# Proto-Pi.net
KiCad netlist of a schematic drawn in EAGLE
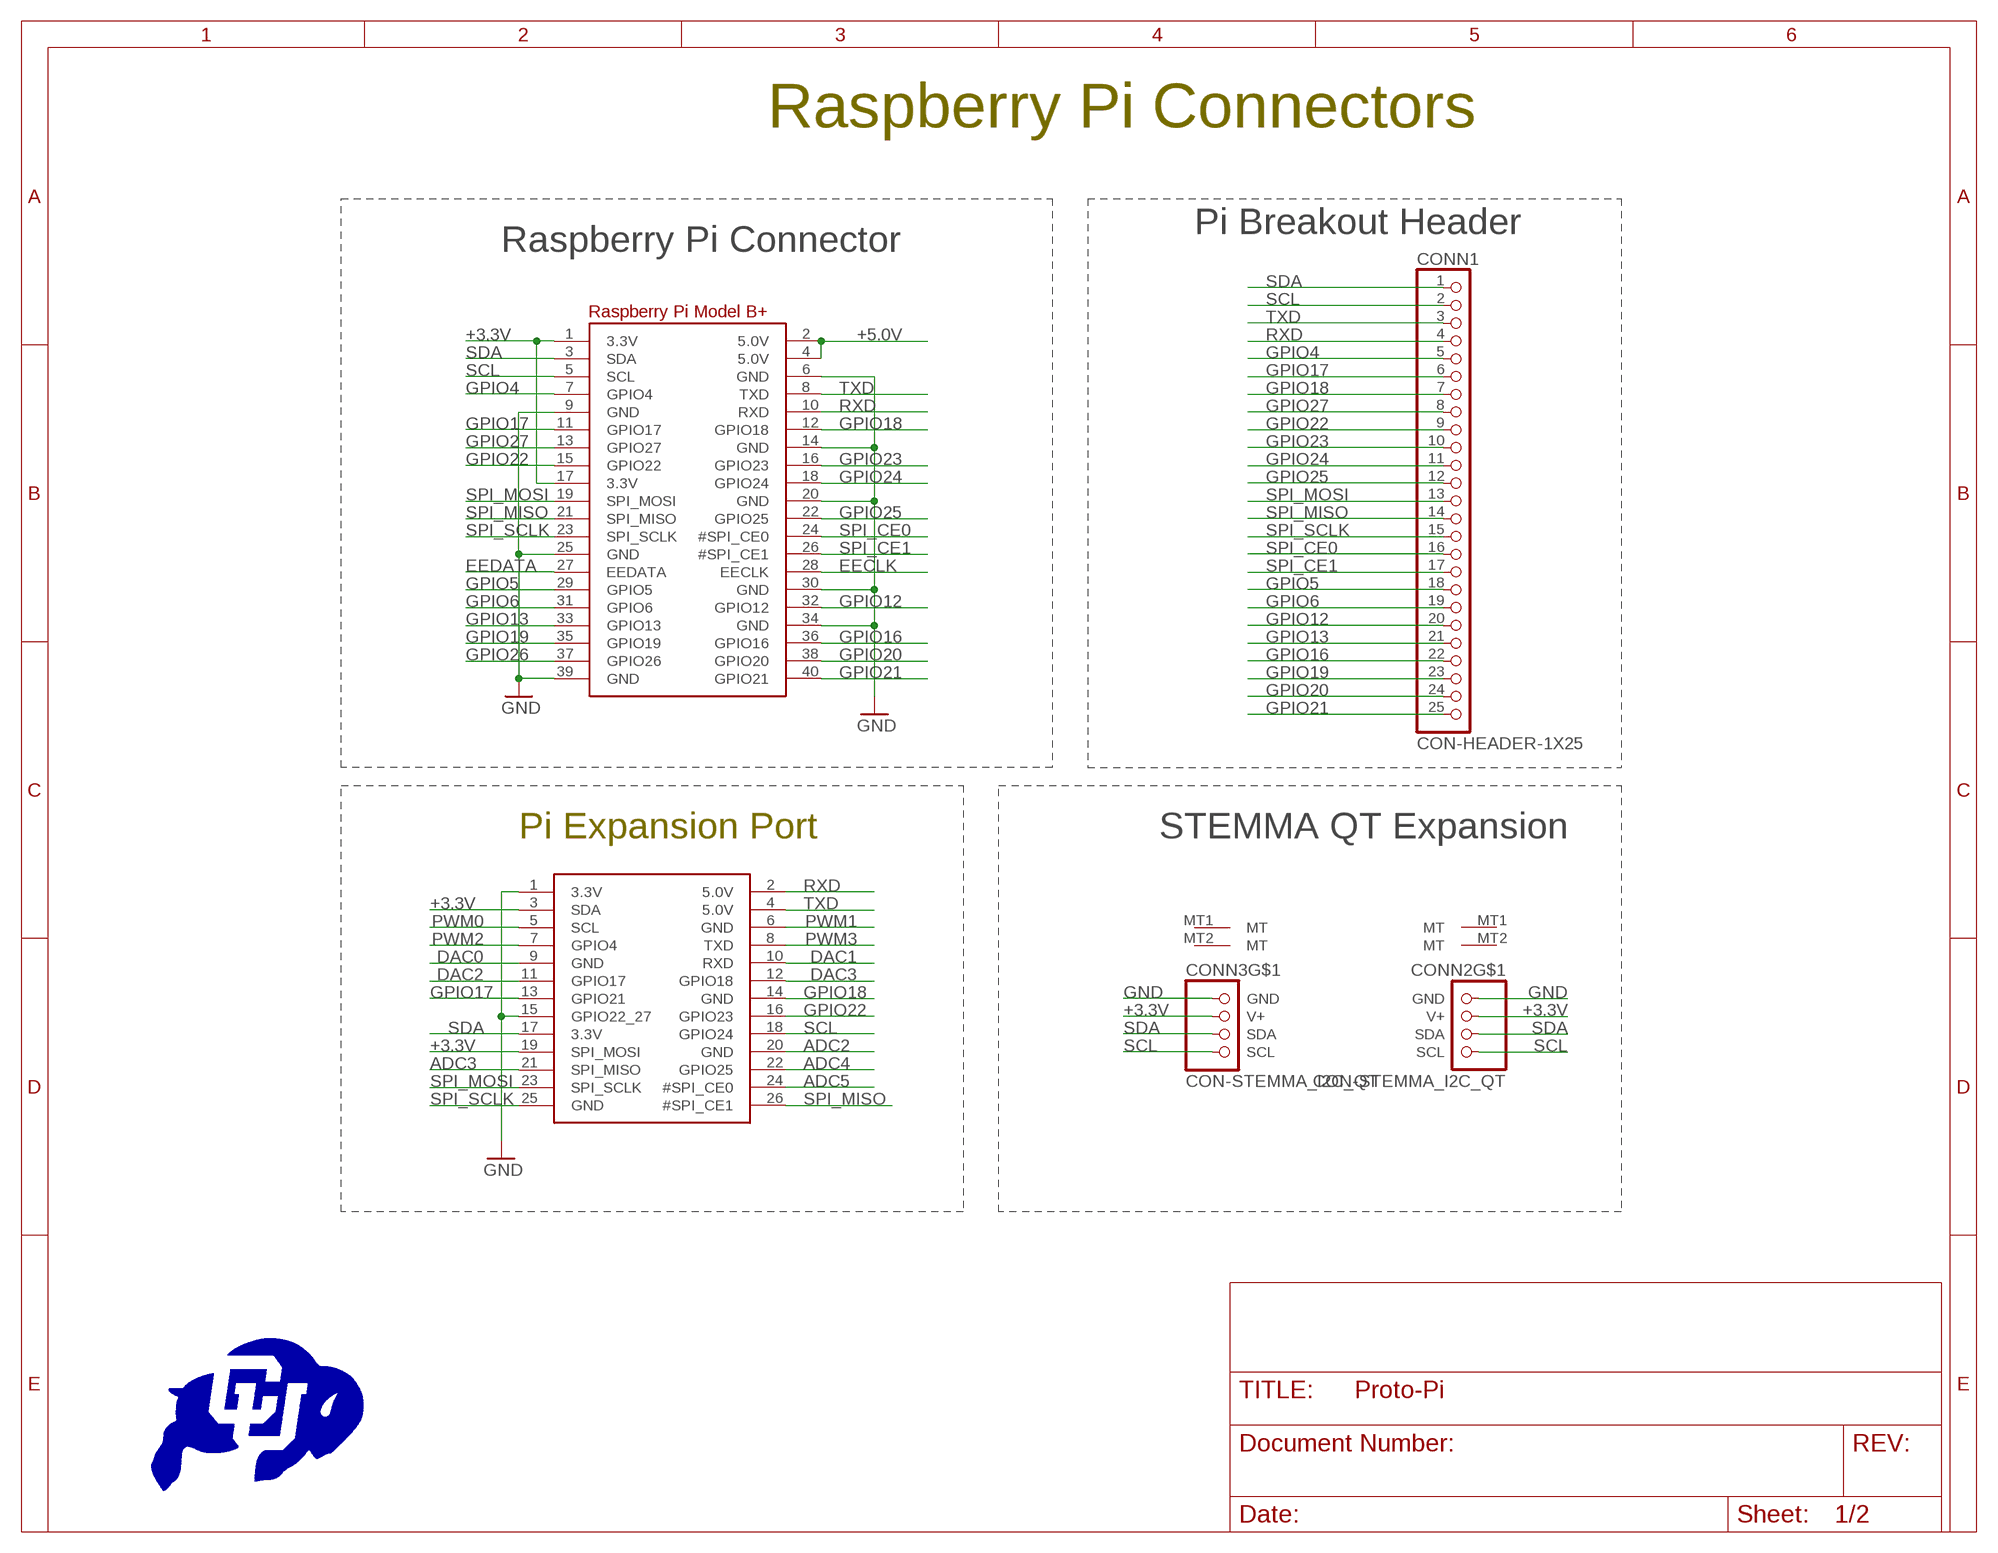
[diagram p0: schematic, sheet 1]
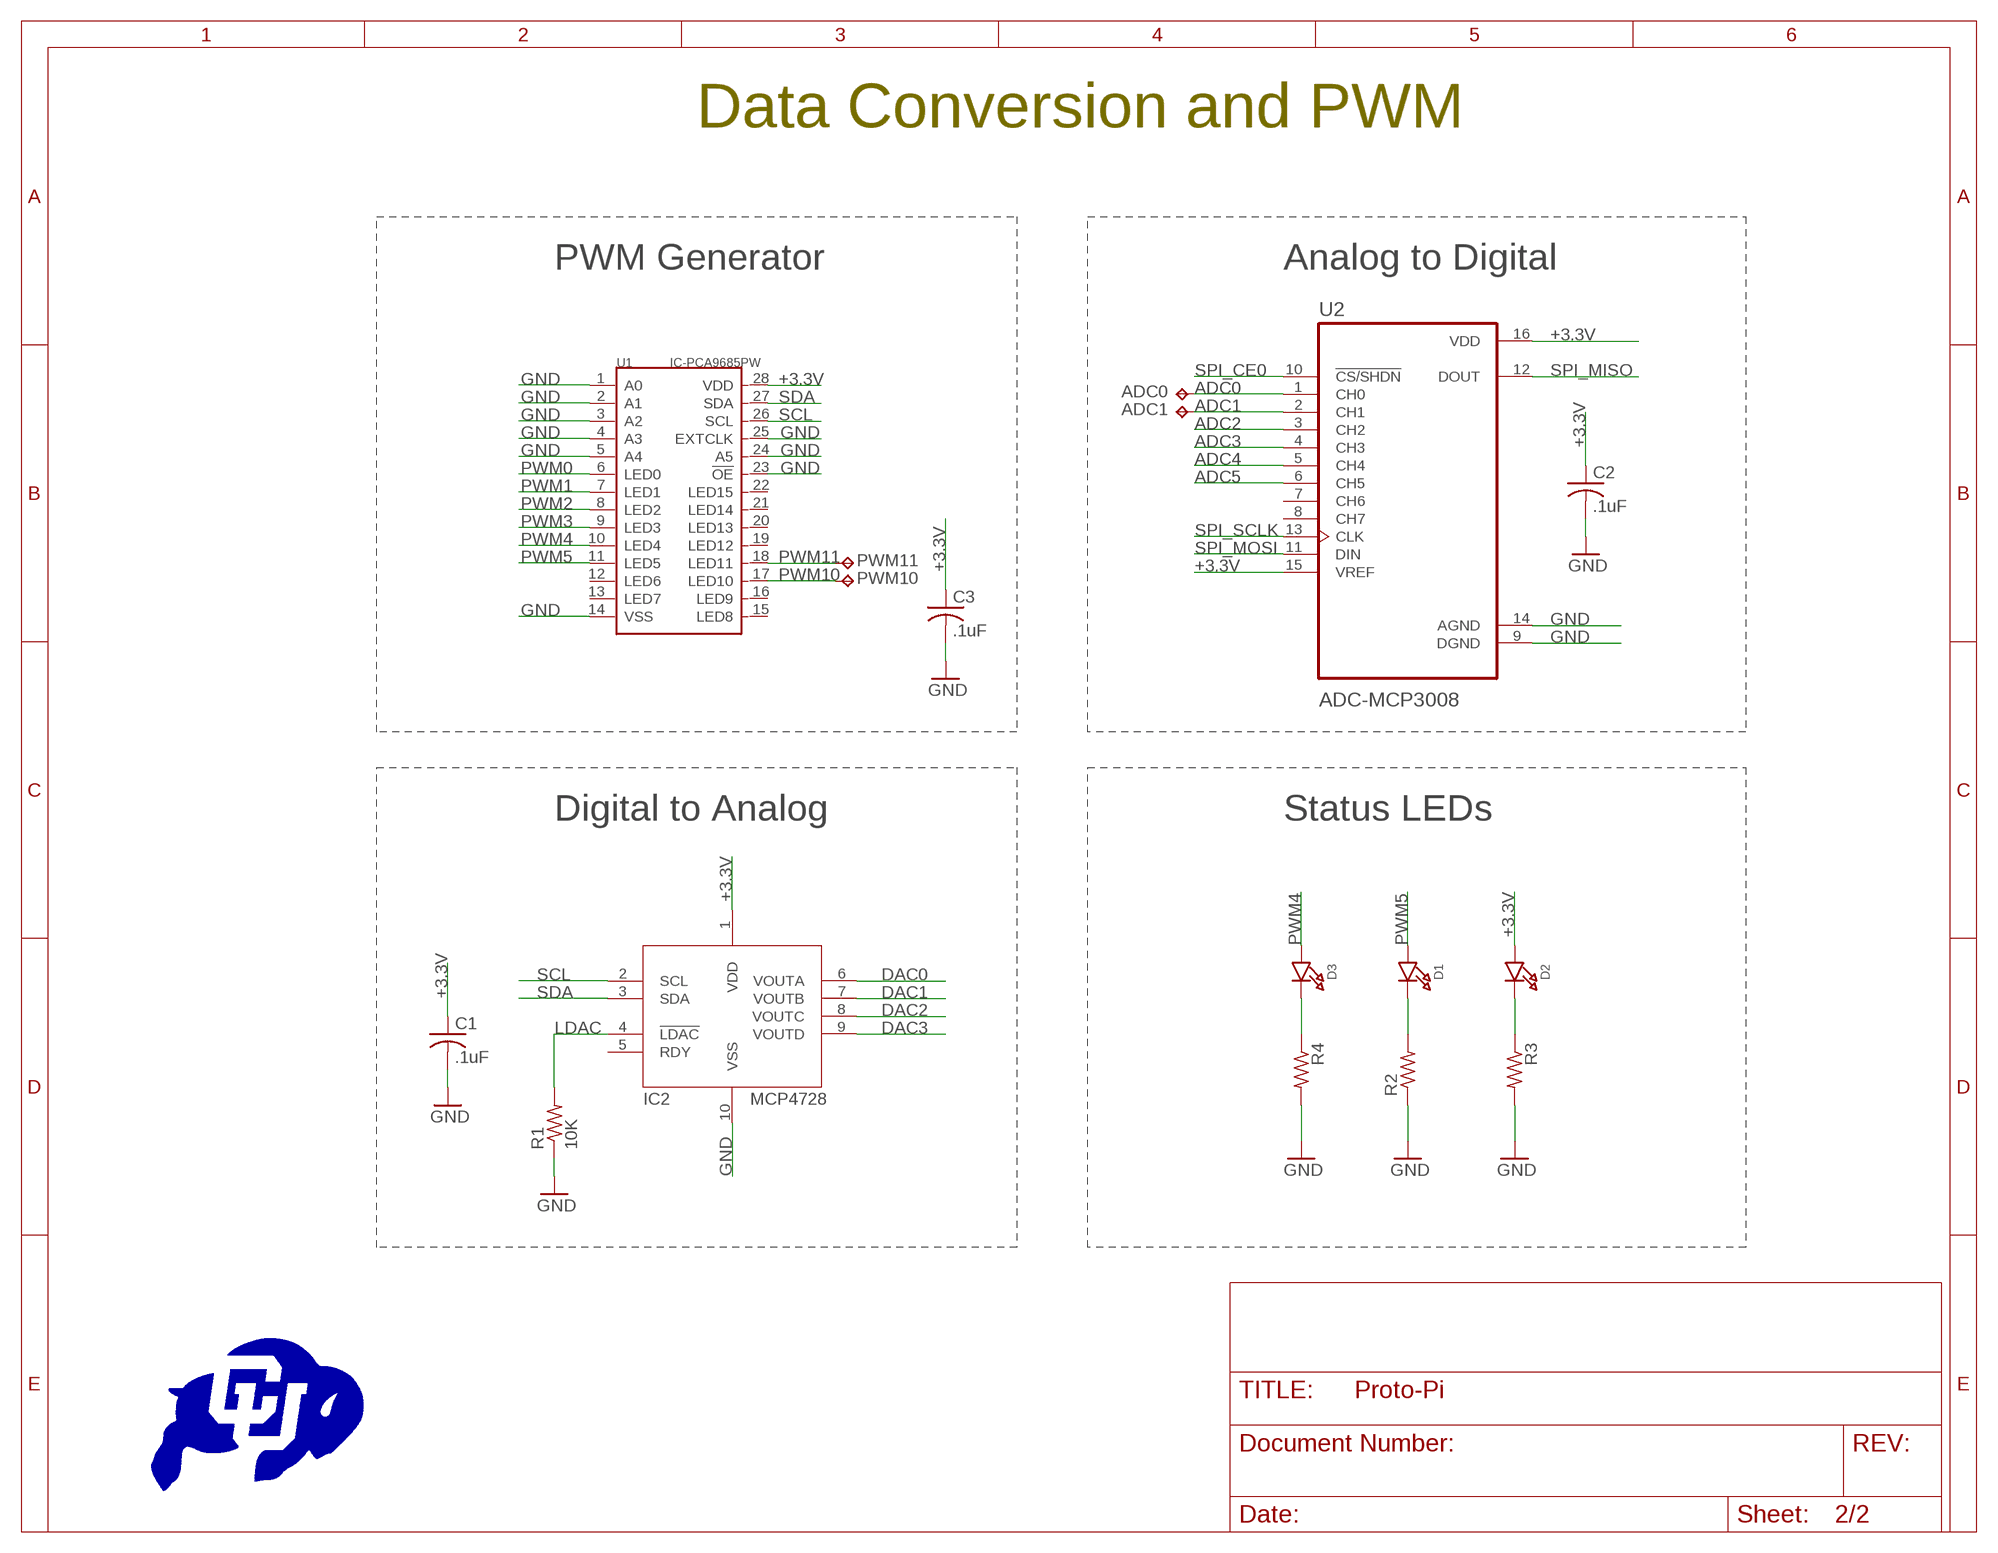
[diagram p1: schematic, sheet 2]

(export (version "E")
  (design (tool "Eeschema 10.0.6"))
  (components
    (comp (ref "CONN1")
      (value "CON-HEADER-1X25")
      (footprint "eagle-import:1X25_ROUND_70MIL")
      (libsource (lib "eagle-import") (part "CON-HEADER-1X25"))
    )
    (comp (ref "CONN2")
      (value "CON-STEMMA_I2C_QT")
      (footprint "eagle-import:JST_SH4")
      (libsource (lib "eagle-import") (part "CON-STEMMA_I2C_QT"))
    )
    (comp (ref "CONN3")
      (value "CON-STEMMA_I2C_QT")
      (footprint "eagle-import:JST_SH4")
      (libsource (lib "eagle-import") (part "CON-STEMMA_I2C_QT"))
    )
    (comp (ref "JP1")
      (value "CON-RASBERRYPI_IDC")
      (footprint "eagle-import:RASBERRYPI_IDC")
      (libsource (lib "eagle-import") (part "CON-RASBERRYPI_IDC"))
    )
    (comp (ref "P1")
      (value "ART-CU-LOGO")
      (footprint "eagle-import:CU_LOGO")
      (libsource (lib "eagle-import") (part "ART-CU-LOGO"))
    )
    (comp (ref "RPI1")
      (value "BRD-RASPBERRYPI_BPLUS_BONNETNODIM")
      (footprint "eagle-import:PI_BONNET_NODIM")
      (libsource (lib "eagle-import") (part "BRD-RASPBERRYPI_BPLUS_BONNETNODIM"))
    )
    (comp (ref "ADC0")
      (value "TPTP20R")
      (footprint "eagle-import:TP20R")
      (libsource (lib "eagle-import") (part "TPTP20R"))
    )
    (comp (ref "ADC1")
      (value "TPTP20R")
      (footprint "eagle-import:TP20R")
      (libsource (lib "eagle-import") (part "TPTP20R"))
    )
    (comp (ref "C1")
      (value ".1uF")
      (footprint "eagle-import:C0603")
      (fields (field (name "MANUFACTURER") "?"))
      (libsource (lib "eagle-import") (part "C-USC0603"))
    )
    (comp (ref "C2")
      (value ".1uF")
      (footprint "eagle-import:C0603")
      (fields (field (name "MANUFACTURER") "?"))
      (libsource (lib "eagle-import") (part "C-USC0603"))
    )
    (comp (ref "C3")
      (value ".1uF")
      (footprint "eagle-import:C0603")
      (fields (field (name "MANUFACTURER") "?"))
      (libsource (lib "eagle-import") (part "C-USC0603"))
    )
    (comp (ref "D1")
      (value "LED-SMA0603_NOOUTLINE")
      (footprint "eagle-import:CHIPLED_0603_NOOUTLINE")
      (libsource (lib "eagle-import") (part "LED-SMA0603_NOOUTLINE"))
    )
    (comp (ref "D2")
      (value "LED-SMA0603_NOOUTLINE")
      (footprint "eagle-import:CHIPLED_0603_NOOUTLINE")
      (libsource (lib "eagle-import") (part "LED-SMA0603_NOOUTLINE"))
    )
    (comp (ref "D3")
      (value "LED-SMA0603_NOOUTLINE")
      (footprint "eagle-import:CHIPLED_0603_NOOUTLINE")
      (libsource (lib "eagle-import") (part "LED-SMA0603_NOOUTLINE"))
    )
    (comp (ref "IC2")
      (value "DAC-MCP4728")
      (footprint "eagle-import:MSOP10")
      (fields (field (name "MANUFACTURER") "?"))
      (libsource (lib "eagle-import") (part "DAC-MCP4728"))
    )
    (comp (ref "P2")
      (value "ART-CU-LOGO")
      (footprint "eagle-import:CU_LOGO")
      (libsource (lib "eagle-import") (part "ART-CU-LOGO"))
    )
    (comp (ref "PWM10")
      (value "TPTP20R")
      (footprint "eagle-import:TP20R")
      (libsource (lib "eagle-import") (part "TPTP20R"))
    )
    (comp (ref "PWM11")
      (value "TPTP20R")
      (footprint "eagle-import:TP20R")
      (libsource (lib "eagle-import") (part "TPTP20R"))
    )
    (comp (ref "R1")
      (value "10K")
      (footprint "eagle-import:R0603")
      (fields (field (name "MANUFACTURER") "?"))
      (libsource (lib "eagle-import") (part "R-US_R0603"))
    )
    (comp (ref "R2")
      (value "R-US_R0402")
      (footprint "eagle-import:R0402")
      (fields (field (name "MANUFACTURER") "?"))
      (libsource (lib "eagle-import") (part "R-US_R0402"))
    )
    (comp (ref "R3")
      (value "R-US_R0402")
      (footprint "eagle-import:R0402")
      (fields (field (name "MANUFACTURER") "?"))
      (libsource (lib "eagle-import") (part "R-US_R0402"))
    )
    (comp (ref "R4")
      (value "R-US_R0402")
      (footprint "eagle-import:R0402")
      (fields (field (name "MANUFACTURER") "?"))
      (libsource (lib "eagle-import") (part "R-US_R0402"))
    )
    (comp (ref "U1")
      (value "IC-PCA9685PW")
      (footprint "eagle-import:TSSOP28-0.65-9.7X4.4MM")
      (fields (field (name "MANUFACTURER") "?"))
      (libsource (lib "eagle-import") (part "IC-PCA9685PW"))
    )
    (comp (ref "U2")
      (value "ADC-MCP3008")
      (footprint "eagle-import:SOIC127P600X175-16N")
      (fields (field (name "MANUFACTURER") "?"))
      (libsource (lib "eagle-import") (part "ADC-MCP3008"))
    )
  )
  (nets
    (net (code "1") (name "+3.3V") (class "Default")
      (node (ref "C1") (pin "1") (pinfunction "1_1") (pintype "passive"))
      (node (ref "C2") (pin "1") (pinfunction "1_1") (pintype "passive"))
      (node (ref "C3") (pin "1") (pinfunction "1_1") (pintype "passive"))
      (node (ref "CONN2") (pin "2") (pinfunction "V+_2") (pintype "passive"))
      (node (ref "CONN3") (pin "2") (pinfunction "V+_2") (pintype "passive"))
      (node (ref "D2") (pin "A") (pinfunction "A_A") (pintype "passive"))
      (node (ref "IC2") (pin "1") (pinfunction "VDD_1") (pintype "power_in"))
      (node (ref "JP1") (pin "19") (pinfunction "SPI_MOSI_19") (pintype "bidirectional"))
      (node (ref "JP1") (pin "3") (pinfunction "SDA_3") (pintype "bidirectional"))
      (node (ref "RPI1") (pin "1") (pinfunction "3.3V_1") (pintype "power_in"))
      (node (ref "RPI1") (pin "17") (pinfunction "3.3V_17") (pintype "power_in"))
      (node (ref "U1") (pin "28") (pinfunction "VDD_28") (pintype "bidirectional"))
      (node (ref "U2") (pin "15") (pinfunction "VREF_15") (pintype "input"))
      (node (ref "U2") (pin "16") (pinfunction "VDD_16") (pintype "power_in"))
    )
    (net (code "2") (name "+5.0V") (class "Default")
      (node (ref "RPI1") (pin "2") (pinfunction "5.0V_2") (pintype "power_in"))
      (node (ref "RPI1") (pin "4") (pinfunction "5.0V_4") (pintype "power_in"))
    )
    (net (code "3") (name "ADC0") (class "Default")
      (node (ref "ADC0") (pin "TP") (pinfunction "TP_TP") (pintype "input"))
      (node (ref "U2") (pin "1") (pinfunction "CH0_1") (pintype "input"))
    )
    (net (code "4") (name "ADC1") (class "Default")
      (node (ref "ADC1") (pin "TP") (pinfunction "TP_TP") (pintype "input"))
      (node (ref "U2") (pin "2") (pinfunction "CH1_2") (pintype "input"))
    )
    (net (code "5") (name "ADC2") (class "Default")
      (node (ref "JP1") (pin "20") (pinfunction "GND_20") (pintype "power_in"))
      (node (ref "U2") (pin "3") (pinfunction "CH2_3") (pintype "input"))
    )
    (net (code "6") (name "ADC3") (class "Default")
      (node (ref "JP1") (pin "21") (pinfunction "SPI_MISO_21") (pintype "input"))
      (node (ref "U2") (pin "4") (pinfunction "CH3_4") (pintype "input"))
    )
    (net (code "7") (name "ADC4") (class "Default")
      (node (ref "JP1") (pin "22") (pinfunction "GPIO25_22") (pintype "bidirectional"))
      (node (ref "U2") (pin "5") (pinfunction "CH4_5") (pintype "input"))
    )
    (net (code "8") (name "ADC5") (class "Default")
      (node (ref "JP1") (pin "24") (pinfunction "#SPI_CE0_24") (pintype "bidirectional"))
      (node (ref "U2") (pin "6") (pinfunction "CH5_6") (pintype "input"))
    )
    (net (code "9") (name "DAC0") (class "Default")
      (node (ref "IC2") (pin "6") (pinfunction "VOUTA_6") (pintype "output"))
      (node (ref "JP1") (pin "9") (pinfunction "GND_9") (pintype "power_in"))
    )
    (net (code "10") (name "DAC1") (class "Default")
      (node (ref "IC2") (pin "7") (pinfunction "VOUTB_7") (pintype "output"))
      (node (ref "JP1") (pin "10") (pinfunction "RXD_10") (pintype "input"))
    )
    (net (code "11") (name "DAC2") (class "Default")
      (node (ref "IC2") (pin "8") (pinfunction "VOUTC_8") (pintype "output"))
      (node (ref "JP1") (pin "11") (pinfunction "GPIO17_11") (pintype "bidirectional"))
    )
    (net (code "12") (name "DAC3") (class "Default")
      (node (ref "IC2") (pin "9") (pinfunction "VOUTD_9") (pintype "output"))
      (node (ref "JP1") (pin "12") (pinfunction "GPIO18_12") (pintype "bidirectional"))
    )
    (net (code "13") (name "EECLK") (class "Default")
      (node (ref "RPI1") (pin "28") (pinfunction "EECLK_28") (pintype "bidirectional"))
    )
    (net (code "14") (name "EEDATA") (class "Default")
      (node (ref "RPI1") (pin "27") (pinfunction "EEDATA_27") (pintype "bidirectional"))
    )
    (net (code "15") (name "GND") (class "Default")
      (node (ref "C1") (pin "2") (pinfunction "2_2") (pintype "passive"))
      (node (ref "C2") (pin "2") (pinfunction "2_2") (pintype "passive"))
      (node (ref "C3") (pin "2") (pinfunction "2_2") (pintype "passive"))
      (node (ref "CONN2") (pin "1") (pinfunction "GND_1") (pintype "passive"))
      (node (ref "CONN3") (pin "1") (pinfunction "GND_1") (pintype "passive"))
      (node (ref "IC2") (pin "10") (pinfunction "VSS_10") (pintype "power_in"))
      (node (ref "JP1") (pin "1") (pinfunction "3.3V_1") (pintype "power_in"))
      (node (ref "JP1") (pin "15") (pinfunction "GPIO22_27_15") (pintype "bidirectional"))
      (node (ref "R1") (pin "1") (pinfunction "1_1") (pintype "passive"))
      (node (ref "R2") (pin "1") (pinfunction "1_1") (pintype "passive"))
      (node (ref "R3") (pin "2") (pinfunction "2_2") (pintype "passive"))
      (node (ref "R4") (pin "2") (pinfunction "2_2") (pintype "passive"))
      (node (ref "RPI1") (pin "14") (pinfunction "GND_14") (pintype "power_in"))
      (node (ref "RPI1") (pin "20") (pinfunction "GND_20") (pintype "power_in"))
      (node (ref "RPI1") (pin "25") (pinfunction "GND_25") (pintype "power_in"))
      (node (ref "RPI1") (pin "30") (pinfunction "GND_30") (pintype "power_in"))
      (node (ref "RPI1") (pin "34") (pinfunction "GND_34") (pintype "power_in"))
      (node (ref "RPI1") (pin "39") (pinfunction "GND_39") (pintype "power_in"))
      (node (ref "RPI1") (pin "6") (pinfunction "GND_6") (pintype "power_in"))
      (node (ref "RPI1") (pin "9") (pinfunction "GND_9") (pintype "power_in"))
      (node (ref "U1") (pin "1") (pinfunction "A0_1") (pintype "bidirectional"))
      (node (ref "U1") (pin "14") (pinfunction "VSS_14") (pintype "bidirectional"))
      (node (ref "U1") (pin "2") (pinfunction "A1_2") (pintype "bidirectional"))
      (node (ref "U1") (pin "23") (pinfunction "~{OE}_23") (pintype "bidirectional"))
      (node (ref "U1") (pin "24") (pinfunction "A5_24") (pintype "bidirectional"))
      (node (ref "U1") (pin "25") (pinfunction "EXTCLK_25") (pintype "bidirectional"))
      (node (ref "U1") (pin "3") (pinfunction "A2_3") (pintype "bidirectional"))
      (node (ref "U1") (pin "4") (pinfunction "A3_4") (pintype "bidirectional"))
      (node (ref "U1") (pin "5") (pinfunction "A4_5") (pintype "bidirectional"))
      (node (ref "U2") (pin "14") (pinfunction "AGND_14") (pintype "power_in"))
      (node (ref "U2") (pin "9") (pinfunction "DGND_9") (pintype "power_in"))
    )
    (net (code "16") (name "GPIO4") (class "Default")
      (node (ref "CONN1") (pin "5") (pinfunction "5_5") (pintype "passive"))
      (node (ref "RPI1") (pin "7") (pinfunction "GPIO4_7") (pintype "bidirectional"))
    )
    (net (code "17") (name "GPIO5") (class "Default")
      (node (ref "CONN1") (pin "18") (pinfunction "18_18") (pintype "passive"))
      (node (ref "RPI1") (pin "29") (pinfunction "GPIO5_29") (pintype "bidirectional"))
    )
    (net (code "18") (name "GPIO6") (class "Default")
      (node (ref "CONN1") (pin "19") (pinfunction "19_19") (pintype "passive"))
      (node (ref "RPI1") (pin "31") (pinfunction "GPIO6_31") (pintype "bidirectional"))
    )
    (net (code "19") (name "GPIO12") (class "Default")
      (node (ref "CONN1") (pin "20") (pinfunction "20_20") (pintype "passive"))
      (node (ref "RPI1") (pin "32") (pinfunction "GPIO12_32") (pintype "bidirectional"))
    )
    (net (code "20") (name "GPIO13") (class "Default")
      (node (ref "CONN1") (pin "21") (pinfunction "21_21") (pintype "passive"))
      (node (ref "RPI1") (pin "33") (pinfunction "GPIO13_33") (pintype "bidirectional"))
    )
    (net (code "21") (name "GPIO16") (class "Default")
      (node (ref "CONN1") (pin "22") (pinfunction "22_22") (pintype "passive"))
      (node (ref "RPI1") (pin "36") (pinfunction "GPIO16_36") (pintype "bidirectional"))
    )
    (net (code "22") (name "GPIO17") (class "Default")
      (node (ref "CONN1") (pin "6") (pinfunction "6_6") (pintype "passive"))
      (node (ref "JP1") (pin "13") (pinfunction "GPIO21_13") (pintype "bidirectional"))
      (node (ref "RPI1") (pin "11") (pinfunction "GPIO17_11") (pintype "bidirectional"))
    )
    (net (code "23") (name "GPIO18") (class "Default")
      (node (ref "CONN1") (pin "7") (pinfunction "7_7") (pintype "passive"))
      (node (ref "JP1") (pin "14") (pinfunction "GND_14") (pintype "power_in"))
      (node (ref "RPI1") (pin "12") (pinfunction "GPIO18_12") (pintype "bidirectional"))
    )
    (net (code "24") (name "GPIO19") (class "Default")
      (node (ref "CONN1") (pin "23") (pinfunction "23_23") (pintype "passive"))
      (node (ref "RPI1") (pin "35") (pinfunction "GPIO19_35") (pintype "bidirectional"))
    )
    (net (code "25") (name "GPIO20") (class "Default")
      (node (ref "CONN1") (pin "24") (pinfunction "24_24") (pintype "passive"))
      (node (ref "RPI1") (pin "38") (pinfunction "GPIO20_38") (pintype "bidirectional"))
    )
    (net (code "26") (name "GPIO21") (class "Default")
      (node (ref "CONN1") (pin "25") (pinfunction "25_25") (pintype "passive"))
      (node (ref "RPI1") (pin "40") (pinfunction "GPIO21_40") (pintype "bidirectional"))
    )
    (net (code "27") (name "GPIO22") (class "Default")
      (node (ref "CONN1") (pin "9") (pinfunction "9_9") (pintype "passive"))
      (node (ref "JP1") (pin "16") (pinfunction "GPIO23_16") (pintype "bidirectional"))
      (node (ref "RPI1") (pin "15") (pinfunction "GPIO22_15") (pintype "bidirectional"))
    )
    (net (code "28") (name "GPIO23") (class "Default")
      (node (ref "CONN1") (pin "10") (pinfunction "10_10") (pintype "passive"))
      (node (ref "RPI1") (pin "16") (pinfunction "GPIO23_16") (pintype "bidirectional"))
    )
    (net (code "29") (name "GPIO24") (class "Default")
      (node (ref "CONN1") (pin "11") (pinfunction "11_11") (pintype "passive"))
      (node (ref "RPI1") (pin "18") (pinfunction "GPIO24_18") (pintype "bidirectional"))
    )
    (net (code "30") (name "GPIO25") (class "Default")
      (node (ref "CONN1") (pin "12") (pinfunction "12_12") (pintype "passive"))
      (node (ref "RPI1") (pin "22") (pinfunction "GPIO25_22") (pintype "bidirectional"))
    )
    (net (code "31") (name "GPIO26") (class "Default")
      (node (ref "RPI1") (pin "37") (pinfunction "GPIO26_37") (pintype "bidirectional"))
    )
    (net (code "32") (name "GPIO27") (class "Default")
      (node (ref "CONN1") (pin "8") (pinfunction "8_8") (pintype "passive"))
      (node (ref "RPI1") (pin "13") (pinfunction "GPIO27_13") (pintype "bidirectional"))
    )
    (net (code "33") (name "LDAC") (class "Default")
      (node (ref "IC2") (pin "4") (pinfunction "~{LDAC}_4") (pintype "input"))
      (node (ref "R1") (pin "2") (pinfunction "2_2") (pintype "passive"))
    )
    (net (code "34") (name "Net-(D1-PadC)") (class "Default")
      (node (ref "D1") (pin "C") (pinfunction "C_C") (pintype "passive"))
      (node (ref "R2") (pin "2") (pinfunction "2_2") (pintype "passive"))
    )
    (net (code "35") (name "Net-(D2-PadC)") (class "Default")
      (node (ref "D2") (pin "C") (pinfunction "C_C") (pintype "passive"))
      (node (ref "R3") (pin "1") (pinfunction "1_1") (pintype "passive"))
    )
    (net (code "36") (name "Net-(D3-PadC)") (class "Default")
      (node (ref "D3") (pin "C") (pinfunction "C_C") (pintype "passive"))
      (node (ref "R4") (pin "1") (pinfunction "1_1") (pintype "passive"))
    )
    (net (code "37") (name "PWM0") (class "Default")
      (node (ref "JP1") (pin "5") (pinfunction "SCL_5") (pintype "bidirectional"))
      (node (ref "U1") (pin "6") (pinfunction "LED0_6") (pintype "bidirectional"))
    )
    (net (code "38") (name "PWM1") (class "Default")
      (node (ref "JP1") (pin "6") (pinfunction "GND_6") (pintype "power_in"))
      (node (ref "U1") (pin "7") (pinfunction "LED1_7") (pintype "bidirectional"))
    )
    (net (code "39") (name "PWM2") (class "Default")
      (node (ref "JP1") (pin "7") (pinfunction "GPIO4_7") (pintype "bidirectional"))
      (node (ref "U1") (pin "8") (pinfunction "LED2_8") (pintype "bidirectional"))
    )
    (net (code "40") (name "PWM3") (class "Default")
      (node (ref "JP1") (pin "8") (pinfunction "TXD_8") (pintype "output"))
      (node (ref "U1") (pin "9") (pinfunction "LED3_9") (pintype "bidirectional"))
    )
    (net (code "41") (name "PWM4") (class "Default")
      (node (ref "D3") (pin "A") (pinfunction "A_A") (pintype "passive"))
      (node (ref "U1") (pin "10") (pinfunction "LED4_10") (pintype "bidirectional"))
    )
    (net (code "42") (name "PWM5") (class "Default")
      (node (ref "D1") (pin "A") (pinfunction "A_A") (pintype "passive"))
      (node (ref "U1") (pin "11") (pinfunction "LED5_11") (pintype "bidirectional"))
    )
    (net (code "43") (name "PWM10") (class "Default")
      (node (ref "PWM10") (pin "TP") (pinfunction "TP_TP") (pintype "input"))
      (node (ref "U1") (pin "17") (pinfunction "LED10_17") (pintype "bidirectional"))
    )
    (net (code "44") (name "PWM11") (class "Default")
      (node (ref "PWM11") (pin "TP") (pinfunction "TP_TP") (pintype "input"))
      (node (ref "U1") (pin "18") (pinfunction "LED11_18") (pintype "bidirectional"))
    )
    (net (code "45") (name "RXD") (class "Default")
      (node (ref "CONN1") (pin "4") (pinfunction "4_4") (pintype "passive"))
      (node (ref "JP1") (pin "2") (pinfunction "5.0V_2") (pintype "power_in"))
      (node (ref "RPI1") (pin "10") (pinfunction "RXD_10") (pintype "bidirectional"))
    )
    (net (code "46") (name "SCL") (class "Default")
      (node (ref "CONN1") (pin "2") (pinfunction "2_2") (pintype "passive"))
      (node (ref "CONN2") (pin "4") (pinfunction "SCL_4") (pintype "passive"))
      (node (ref "CONN3") (pin "4") (pinfunction "SCL_4") (pintype "passive"))
      (node (ref "IC2") (pin "2") (pinfunction "SCL_2") (pintype "bidirectional"))
      (node (ref "JP1") (pin "18") (pinfunction "GPIO24_18") (pintype "bidirectional"))
      (node (ref "RPI1") (pin "5") (pinfunction "SCL_5") (pintype "bidirectional"))
      (node (ref "U1") (pin "26") (pinfunction "SCL_26") (pintype "bidirectional"))
    )
    (net (code "47") (name "SDA") (class "Default")
      (node (ref "CONN1") (pin "1") (pinfunction "1_1") (pintype "passive"))
      (node (ref "CONN2") (pin "3") (pinfunction "SDA_3") (pintype "passive"))
      (node (ref "CONN3") (pin "3") (pinfunction "SDA_3") (pintype "passive"))
      (node (ref "IC2") (pin "3") (pinfunction "SDA_3") (pintype "bidirectional"))
      (node (ref "JP1") (pin "17") (pinfunction "3.3V_17") (pintype "power_in"))
      (node (ref "RPI1") (pin "3") (pinfunction "SDA_3") (pintype "bidirectional"))
      (node (ref "U1") (pin "27") (pinfunction "SDA_27") (pintype "bidirectional"))
    )
    (net (code "48") (name "SPI_CE0") (class "Default")
      (node (ref "CONN1") (pin "16") (pinfunction "16_16") (pintype "passive"))
      (node (ref "RPI1") (pin "24") (pinfunction "#SPI_CE0_24") (pintype "bidirectional"))
      (node (ref "U2") (pin "10") (pinfunction "~{CS/SHDN}_10") (pintype "input"))
    )
    (net (code "49") (name "SPI_CE1") (class "Default")
      (node (ref "CONN1") (pin "17") (pinfunction "17_17") (pintype "passive"))
      (node (ref "RPI1") (pin "26") (pinfunction "#SPI_CE1_26") (pintype "bidirectional"))
    )
    (net (code "50") (name "SPI_MISO") (class "Default")
      (node (ref "CONN1") (pin "14") (pinfunction "14_14") (pintype "passive"))
      (node (ref "JP1") (pin "26") (pinfunction "#SPI_CE1_26") (pintype "bidirectional"))
      (node (ref "RPI1") (pin "21") (pinfunction "SPI_MISO_21") (pintype "bidirectional"))
      (node (ref "U2") (pin "12") (pinfunction "DOUT_12") (pintype "output"))
    )
    (net (code "51") (name "SPI_MOSI") (class "Default")
      (node (ref "CONN1") (pin "13") (pinfunction "13_13") (pintype "passive"))
      (node (ref "JP1") (pin "23") (pinfunction "SPI_SCLK_23") (pintype "bidirectional"))
      (node (ref "RPI1") (pin "19") (pinfunction "SPI_MOSI_19") (pintype "bidirectional"))
      (node (ref "U2") (pin "11") (pinfunction "DIN_11") (pintype "input"))
    )
    (net (code "52") (name "SPI_SCLK") (class "Default")
      (node (ref "CONN1") (pin "15") (pinfunction "15_15") (pintype "passive"))
      (node (ref "JP1") (pin "25") (pinfunction "GND_25") (pintype "power_in"))
      (node (ref "RPI1") (pin "23") (pinfunction "SPI_SCLK_23") (pintype "bidirectional"))
      (node (ref "U2") (pin "13") (pinfunction "CLK_13") (pintype "input"))
    )
    (net (code "53") (name "TXD") (class "Default")
      (node (ref "CONN1") (pin "3") (pinfunction "3_3") (pintype "passive"))
      (node (ref "JP1") (pin "4") (pinfunction "5.0V_4") (pintype "power_in"))
      (node (ref "RPI1") (pin "8") (pinfunction "TXD_8") (pintype "bidirectional"))
    )
    (net (code "54") (name "unconnected-(CONN2B-MT-PadMT1)") (class "Default")
      (node (ref "CONN2") (pin "MT1") (pinfunction "MT_MT1") (pintype "bidirectional"))
    )
    (net (code "55") (name "unconnected-(CONN2C-MT-PadMT2)") (class "Default")
      (node (ref "CONN2") (pin "MT2") (pinfunction "MT_MT2") (pintype "bidirectional"))
    )
    (net (code "56") (name "unconnected-(CONN3B-MT-PadMT1)") (class "Default")
      (node (ref "CONN3") (pin "MT1") (pinfunction "MT_MT1") (pintype "bidirectional"))
    )
    (net (code "57") (name "unconnected-(CONN3C-MT-PadMT2)") (class "Default")
      (node (ref "CONN3") (pin "MT2") (pinfunction "MT_MT2") (pintype "bidirectional"))
    )
    (net (code "58") (name "unconnected-(IC2-RDY-Pad5)") (class "Default")
      (node (ref "IC2") (pin "5") (pinfunction "RDY_5") (pintype "output"))
    )
    (net (code "59") (name "unconnected-(U1-LED6-Pad12)") (class "Default")
      (node (ref "U1") (pin "12") (pinfunction "LED6_12") (pintype "bidirectional"))
    )
    (net (code "60") (name "unconnected-(U1-LED7-Pad13)") (class "Default")
      (node (ref "U1") (pin "13") (pinfunction "LED7_13") (pintype "bidirectional"))
    )
    (net (code "61") (name "unconnected-(U1-LED8-Pad15)") (class "Default")
      (node (ref "U1") (pin "15") (pinfunction "LED8_15") (pintype "bidirectional"))
    )
    (net (code "62") (name "unconnected-(U1-LED9-Pad16)") (class "Default")
      (node (ref "U1") (pin "16") (pinfunction "LED9_16") (pintype "bidirectional"))
    )
    (net (code "63") (name "unconnected-(U1-LED12-Pad19)") (class "Default")
      (node (ref "U1") (pin "19") (pinfunction "LED12_19") (pintype "bidirectional"))
    )
    (net (code "64") (name "unconnected-(U1-LED13-Pad20)") (class "Default")
      (node (ref "U1") (pin "20") (pinfunction "LED13_20") (pintype "bidirectional"))
    )
    (net (code "65") (name "unconnected-(U1-LED14-Pad21)") (class "Default")
      (node (ref "U1") (pin "21") (pinfunction "LED14_21") (pintype "bidirectional"))
    )
    (net (code "66") (name "unconnected-(U1-LED15-Pad22)") (class "Default")
      (node (ref "U1") (pin "22") (pinfunction "LED15_22") (pintype "bidirectional"))
    )
    (net (code "67") (name "unconnected-(U2-CH6-Pad7)") (class "Default")
      (node (ref "U2") (pin "7") (pinfunction "CH6_7") (pintype "input"))
    )
    (net (code "68") (name "unconnected-(U2-CH7-Pad8)") (class "Default")
      (node (ref "U2") (pin "8") (pinfunction "CH7_8") (pintype "input"))
    )
  )
)
